# 1-Schematic_TW4_Main_board2.net
KiCad netlist of a schematic drawn in EasyEDA
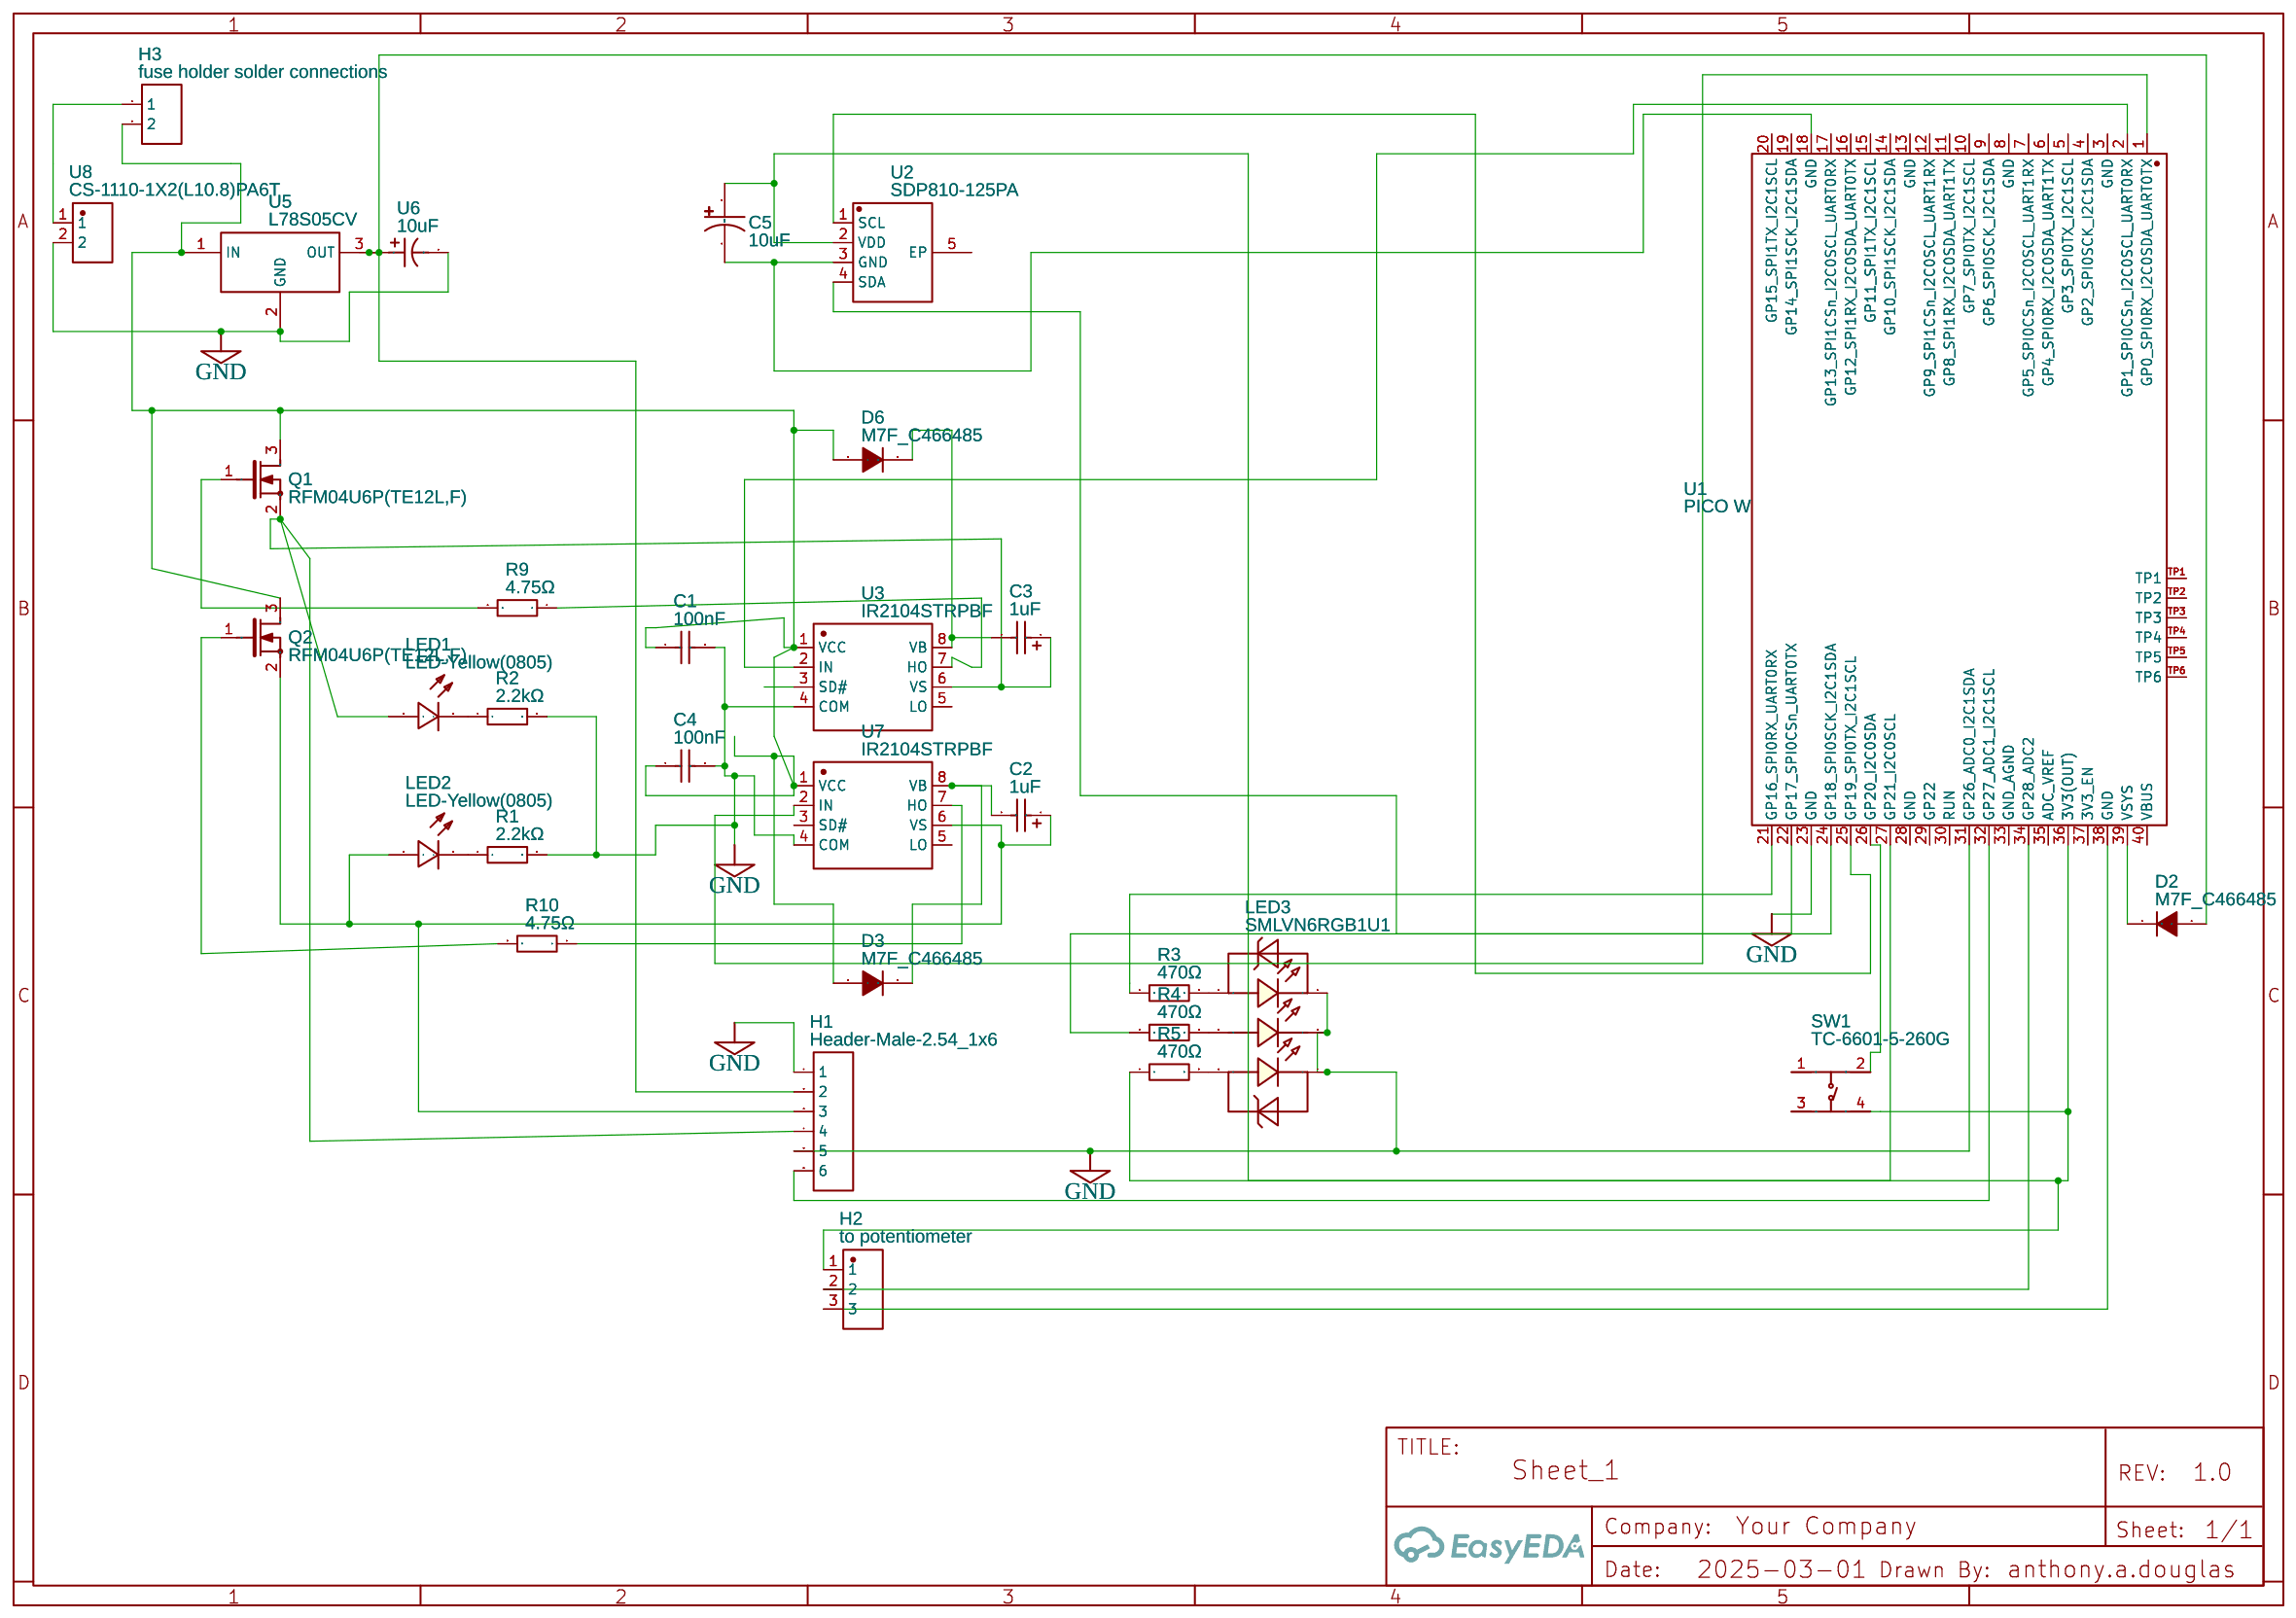
[diagram p0: schematic sheet]

(export (version "E")
  (design (tool "Eeschema 10.0.6"))
  (components
    (comp (ref "C1")
      (value "100nF")
      (fields (field (name "Manufacturer Part") "CGA3E2X7R1H104KT0Y0N") (field (name "Manufacturer") "TDK"))
      (libsource (lib "") (part "CGA3E2X7R1H104KT0Y0N"))
    )
    (comp (ref "C2")
      (value "1uF")
      (fields (field (name "Manufacturer Part") "TAJA105K035RNJ") (field (name "Manufacturer") "Kyocera AVX"))
      (libsource (lib "") (part "TAJA105K035RNJ"))
    )
    (comp (ref "C3")
      (value "1uF")
      (fields (field (name "Manufacturer Part") "TAJA105K035RNJ") (field (name "Manufacturer") "Kyocera AVX"))
      (libsource (lib "") (part "TAJA105K035RNJ"))
    )
    (comp (ref "C4")
      (value "100nF")
      (fields (field (name "Manufacturer Part") "CGA3E2X7R1H104KT0Y0N") (field (name "Manufacturer") "TDK"))
      (libsource (lib "") (part "CGA3E2X7R1H104KT0Y0N"))
    )
    (comp (ref "C5")
      (value "10uF")
      (fields (field (name "Manufacturer Part") "EEEFK1V100AR") (field (name "Manufacturer") "PANASONIC(松下)"))
      (libsource (lib "") (part "EEEFK1V100AR"))
    )
    (comp (ref "D2")
      (value "M7F_C466485")
      (fields (field (name "Manufacturer Part") "M7F") (field (name "Manufacturer") "High Diode(海德)"))
      (libsource (lib "") (part "M7F_C466485"))
    )
    (comp (ref "D3")
      (value "M7F_C466485")
      (fields (field (name "Manufacturer Part") "M7F") (field (name "Manufacturer") "High Diode(海德)"))
      (libsource (lib "") (part "M7F_C466485_1"))
    )
    (comp (ref "D6")
      (value "M7F_C466485")
      (fields (field (name "Manufacturer Part") "M7F") (field (name "Manufacturer") "High Diode(海德)"))
      (libsource (lib "") (part "M7F_C466485_1"))
    )
    (comp (ref "H1")
      (value "Header-Male-2.54_1x6")
      (fields (field (name "Manufacturer Part") "2.54-1x6P直针") (field (name "Manufacturer") "BOOMELE(博穆精密)"))
      (libsource (lib "") (part "Header-Male-2.54_1x6"))
    )
    (comp (ref "H2")
      (value "to potentiometer")
      (fields
        (field (name "Manufacturer Part") "HC-PM254-8.5H-1x3PW-02A")
        (field (name "Manufacturer") "HC(虹成电子)")
      )
      (libsource (lib "") (part "HC-PM254-8.5H-1X3PW"))
    )
    (comp (ref "H3") (value "fuse holder solder connections") (libsource (lib "") (part "HDR-F-2.54_1x2")))
    (comp (ref "LED1")
      (value "LED-Yellow(0805)")
      (fields
        (field (name "Manufacturer Part") "17-21SUYC/TR8")
        (field (name "Manufacturer") "Hubei KENTO Elec")
      )
      (libsource (lib "") (part "LED-Yellow(0805)"))
    )
    (comp (ref "LED2")
      (value "LED-Yellow(0805)")
      (fields
        (field (name "Manufacturer Part") "17-21SUYC/TR8")
        (field (name "Manufacturer") "Hubei KENTO Elec")
      )
      (libsource (lib "") (part "LED-Yellow(0805)"))
    )
    (comp (ref "LED3")
      (value "SMLVN6RGB1U1")
      (fields (field (name "Manufacturer") "ROHM(罗姆)"))
      (libsource (lib "") (part "SMLVN6RGB1U1"))
    )
    (comp (ref "Q1")
      (value "RFM04U6P(TE12L,F)")
      (fields (field (name "Manufacturer") "TOSHIBA(东芝)"))
      (libsource (lib "") (part "RFM04U6P(TE12L,F)"))
    )
    (comp (ref "Q2")
      (value "RFM04U6P(TE12L,F)")
      (fields (field (name "Manufacturer") "TOSHIBA(东芝)"))
      (libsource (lib "") (part "RFM04U6P(TE12L,F)"))
    )
    (comp (ref "R1")
      (value "2.2kΩ")
      (fields
        (field (name "Manufacturer Part") "0603WAF2201T5E")
        (field (name "Manufacturer") "UNI-ROYAL(厚声)")
      )
      (libsource (lib "") (part "0603WAF2201T5E"))
    )
    (comp (ref "R2")
      (value "2.2kΩ")
      (fields
        (field (name "Manufacturer Part") "0603WAF2201T5E")
        (field (name "Manufacturer") "UNI-ROYAL(厚声)")
      )
      (libsource (lib "") (part "0603WAF2201T5E"))
    )
    (comp (ref "R3")
      (value "470Ω")
      (fields
        (field (name "Manufacturer Part") "1206W4F4700T5E")
        (field (name "Manufacturer") "UNI-ROYAL(厚声)")
      )
      (libsource (lib "") (part "1206W4F4700T5E"))
    )
    (comp (ref "R4")
      (value "470Ω")
      (fields
        (field (name "Manufacturer Part") "1206W4F4700T5E")
        (field (name "Manufacturer") "UNI-ROYAL(厚声)")
      )
      (libsource (lib "") (part "1206W4F4700T5E"))
    )
    (comp (ref "R5")
      (value "470Ω")
      (fields
        (field (name "Manufacturer Part") "1206W4F4700T5E")
        (field (name "Manufacturer") "UNI-ROYAL(厚声)")
      )
      (libsource (lib "") (part "1206W4F4700T5E"))
    )
    (comp (ref "R9")
      (value "4.75Ω")
      (fields (field (name "Manufacturer Part") "RTT024R75FTH") (field (name "Manufacturer") "RALEC(旺诠)"))
      (libsource (lib "") (part "RTT024R75FTH"))
    )
    (comp (ref "R10")
      (value "4.75Ω")
      (fields (field (name "Manufacturer Part") "RTT024R75FTH") (field (name "Manufacturer") "RALEC(旺诠)"))
      (libsource (lib "") (part "RTT024R75FTH"))
    )
    (comp (ref "SW1")
      (value "TC-6601-5-260G")
      (fields (field (name "Manufacturer") "HCTL(华灿天禄)"))
      (libsource (lib "") (part "TC-6601-5-260G"))
    )
    (comp (ref "U1")
      (value "PICO W")
      (fields (field (name "Manufacturer") "Raspberry Pi(树莓派)"))
      (libsource (lib "") (part "PICO W"))
    )
    (comp (ref "U2")
      (value "SDP810-125PA")
      (fields
        (field (name "Manufacturer Part") "SDP810-125PA-D")
        (field (name "Manufacturer") "Sensirion(瑞士盛思锐)")
      )
      (libsource (lib "") (part "SDP810-125PA"))
    )
    (comp (ref "U3")
      (value "IR2104STRPBF")
      (fields (field (name "Manufacturer") "Infineon(英飞凌)"))
      (libsource (lib "") (part "IR2104STRPBF"))
    )
    (comp (ref "U5")
      (value "L78S05CV")
      (fields (field (name "Manufacturer") "ST(意法半导体)"))
      (libsource (lib "") (part "L78S05CV"))
    )
    (comp (ref "U6")
      (value "10uF")
      (fields (field (name "Manufacturer Part") "TMCP1A106MTRF") (field (name "Manufacturer") "VISHAY(威世)"))
      (libsource (lib "") (part "TMCP1A106MTRF"))
    )
    (comp (ref "U7")
      (value "IR2104STRPBF")
      (fields (field (name "Manufacturer") "Infineon(英飞凌)"))
      (libsource (lib "") (part "IR2104STRPBF"))
    )
    (comp (ref "U8")
      (value "CS-1110-1X2(L10.8)PA6T")
      (fields (field (name "Manufacturer") "CST(永丰盈)"))
      (libsource (lib "") (part "CS-1110-1X2(L10.8)PA6T"))
    )
  )
  (nets
    (net (code "1") (name "GND") (class "Default")
      (node (ref "C1") (pin "2") (pinfunction "2_2") (pintype "input"))
      (node (ref "C4") (pin "2") (pinfunction "2_2") (pintype "input"))
      (node (ref "H1") (pin "1") (pinfunction "1_1") (pintype "input"))
      (node (ref "H1") (pin "5") (pinfunction "5_5") (pintype "input"))
      (node (ref "LED3") (pin "4") (pinfunction "-_4") (pintype "unspecified"))
      (node (ref "LED3") (pin "5") (pinfunction "-_5") (pintype "unspecified"))
      (node (ref "LED3") (pin "6") (pinfunction "-_6") (pintype "unspecified"))
      (node (ref "R1") (pin "2") (pinfunction "2_2") (pintype "input"))
      (node (ref "R2") (pin "2") (pinfunction "2_2") (pintype "input"))
      (node (ref "U1") (pin "23") (pinfunction "GND_23") (pintype "unspecified"))
      (node (ref "U1") (pin "31") (pinfunction "GP26_ADC0_I2C1SDA_31") (pintype "unspecified"))
      (node (ref "U3") (pin "4") (pinfunction "COM_4") (pintype "unspecified"))
      (node (ref "U5") (pin "2") (pinfunction "GND_2") (pintype "passive"))
      (node (ref "U6") (pin "2") (pinfunction "2_2") (pintype "input"))
      (node (ref "U7") (pin "4") (pinfunction "COM_4") (pintype "unspecified"))
      (node (ref "U8") (pin "2") (pinfunction "2_2") (pintype "unspecified"))
    )
    (net (code "2") (name "Net-(D2-A)") (class "Default")
      (node (ref "D2") (pin "2") (pinfunction "A_2") (pintype "unspecified"))
      (node (ref "H1") (pin "2") (pinfunction "2_2") (pintype "input"))
      (node (ref "U5") (pin "3") (pinfunction "OUT_3") (pintype "passive"))
      (node (ref "U6") (pin "1") (pinfunction "1_1") (pintype "input"))
    )
    (net (code "3") (name "Net-(D2-C)") (class "Default")
      (node (ref "D2") (pin "1") (pinfunction "C_1") (pintype "unspecified"))
      (node (ref "U1") (pin "39") (pinfunction "VSYS_39") (pintype "unspecified"))
    )
    (net (code "4") (name "Net-(D3-A)") (class "Default")
      (node (ref "C1") (pin "1") (pinfunction "1_1") (pintype "input"))
      (node (ref "C4") (pin "1") (pinfunction "1_1") (pintype "input"))
      (node (ref "D3") (pin "2") (pinfunction "A_2") (pintype "unspecified"))
      (node (ref "D6") (pin "2") (pinfunction "A_2") (pintype "unspecified"))
      (node (ref "H3") (pin "2") (pinfunction "2_2") (pintype "input"))
      (node (ref "Q1") (pin "3") (pinfunction "D_3") (pintype "unspecified"))
      (node (ref "Q2") (pin "3") (pinfunction "D_3") (pintype "unspecified"))
      (node (ref "U3") (pin "1") (pinfunction "VCC_1") (pintype "unspecified"))
      (node (ref "U5") (pin "1") (pinfunction "IN_1") (pintype "passive"))
      (node (ref "U7") (pin "1") (pinfunction "VCC_1") (pintype "unspecified"))
    )
    (net (code "5") (name "Net-(D3-C)") (class "Default")
      (node (ref "C2") (pin "2") (pinfunction "2_2") (pintype "input"))
      (node (ref "D3") (pin "1") (pinfunction "C_1") (pintype "unspecified"))
      (node (ref "U7") (pin "8") (pinfunction "VB_8") (pintype "unspecified"))
    )
    (net (code "6") (name "Net-(D6-C)") (class "Default")
      (node (ref "C3") (pin "2") (pinfunction "2_2") (pintype "input"))
      (node (ref "D6") (pin "1") (pinfunction "C_1") (pintype "unspecified"))
      (node (ref "U3") (pin "8") (pinfunction "VB_8") (pintype "unspecified"))
    )
    (net (code "7") (name "Net-(H2-Pad3)") (class "Default")
      (node (ref "H2") (pin "3") (pinfunction "3_3") (pintype "unspecified"))
      (node (ref "U1") (pin "38") (pinfunction "GND_38") (pintype "unspecified"))
    )
    (net (code "8") (name "Net-(H3-Pad1)") (class "Default")
      (node (ref "H3") (pin "1") (pinfunction "1_1") (pintype "input"))
      (node (ref "U8") (pin "1") (pinfunction "1_1") (pintype "unspecified"))
    )
    (net (code "9") (name "Net-(LED1-+)") (class "Default")
      (node (ref "C3") (pin "1") (pinfunction "1_1") (pintype "input"))
      (node (ref "H1") (pin "4") (pinfunction "4_4") (pintype "input"))
      (node (ref "LED1") (pin "1") (pinfunction "+_1") (pintype "unspecified"))
      (node (ref "Q1") (pin "2") (pinfunction "S_2") (pintype "unspecified"))
      (node (ref "U3") (pin "6") (pinfunction "VS_6") (pintype "unspecified"))
    )
    (net (code "10") (name "Net-(LED1--)") (class "Default")
      (node (ref "LED1") (pin "2") (pinfunction "-_2") (pintype "unspecified"))
      (node (ref "R2") (pin "1") (pinfunction "1_1") (pintype "input"))
    )
    (net (code "11") (name "Net-(LED2-+)") (class "Default")
      (node (ref "C2") (pin "1") (pinfunction "1_1") (pintype "input"))
      (node (ref "H1") (pin "3") (pinfunction "3_3") (pintype "input"))
      (node (ref "LED2") (pin "1") (pinfunction "+_1") (pintype "unspecified"))
      (node (ref "Q2") (pin "2") (pinfunction "S_2") (pintype "unspecified"))
      (node (ref "U7") (pin "6") (pinfunction "VS_6") (pintype "unspecified"))
    )
    (net (code "12") (name "Net-(LED2--)") (class "Default")
      (node (ref "LED2") (pin "2") (pinfunction "-_2") (pintype "unspecified"))
      (node (ref "R1") (pin "1") (pinfunction "1_1") (pintype "input"))
    )
    (net (code "13") (name "Net-(LED3-+-Pad1)") (class "Default")
      (node (ref "LED3") (pin "1") (pinfunction "+_1") (pintype "unspecified"))
      (node (ref "R3") (pin "2") (pinfunction "2_2") (pintype "input"))
    )
    (net (code "14") (name "Net-(LED3-+-Pad2)") (class "Default")
      (node (ref "LED3") (pin "2") (pinfunction "+_2") (pintype "unspecified"))
      (node (ref "R4") (pin "2") (pinfunction "2_2") (pintype "input"))
    )
    (net (code "15") (name "Net-(LED3-+-Pad3)") (class "Default")
      (node (ref "LED3") (pin "3") (pinfunction "+_3") (pintype "unspecified"))
      (node (ref "R5") (pin "2") (pinfunction "2_2") (pintype "input"))
    )
    (net (code "16") (name "Net-(Q1-G)") (class "Default")
      (node (ref "Q1") (pin "1") (pinfunction "G_1") (pintype "unspecified"))
      (node (ref "R9") (pin "2") (pinfunction "2_2") (pintype "unspecified"))
    )
    (net (code "17") (name "Net-(Q2-G)") (class "Default")
      (node (ref "Q2") (pin "1") (pinfunction "G_1") (pintype "unspecified"))
      (node (ref "R10") (pin "2") (pinfunction "2_2") (pintype "unspecified"))
    )
    (net (code "18") (name "Net-(U1-3V3(OUT))") (class "Default")
      (node (ref "C5") (pin "1") (pinfunction "1_1") (pintype "unspecified"))
      (node (ref "H2") (pin "1") (pinfunction "1_1") (pintype "unspecified"))
      (node (ref "SW1") (pin "4") (pinfunction "4_4") (pintype "unspecified"))
      (node (ref "U1") (pin "36") (pinfunction "3V3(OUT)_36") (pintype "unspecified"))
      (node (ref "U2") (pin "2") (pinfunction "VDD_2") (pintype "unspecified"))
    )
    (net (code "19") (name "Net-(U1-GP0_SPI0RX_I2C0SDA_UART0TX)") (class "Default")
      (node (ref "U1") (pin "1") (pinfunction "GP0_SPI0RX_I2C0SDA_UART0TX_1") (pintype "unspecified"))
      (node (ref "U7") (pin "2") (pinfunction "IN_2") (pintype "unspecified"))
    )
    (net (code "20") (name "Net-(U1-GP1_SPI0CSn_I2C0SCL_UART0RX)") (class "Default")
      (node (ref "U1") (pin "2") (pinfunction "GP1_SPI0CSn_I2C0SCL_UART0RX_2") (pintype "unspecified"))
      (node (ref "U3") (pin "2") (pinfunction "IN_2") (pintype "unspecified"))
    )
    (net (code "21") (name "Net-(U1-GP16_SPI0RX_UART0RX)") (class "Default")
      (node (ref "R3") (pin "1") (pinfunction "1_1") (pintype "input"))
      (node (ref "U1") (pin "21") (pinfunction "GP16_SPI0RX_UART0RX_21") (pintype "unspecified"))
    )
    (net (code "22") (name "Net-(U1-GP17_SPI0CSn_UART0TX)") (class "Default")
      (node (ref "R4") (pin "1") (pinfunction "1_1") (pintype "input"))
      (node (ref "U1") (pin "22") (pinfunction "GP17_SPI0CSn_UART0TX_22") (pintype "unspecified"))
    )
    (net (code "23") (name "Net-(U1-GP18_SPI0SCK_I2C1SDA)") (class "Default")
      (node (ref "U1") (pin "24") (pinfunction "GP18_SPI0SCK_I2C1SDA_24") (pintype "unspecified"))
      (node (ref "U2") (pin "4") (pinfunction "SDA_4") (pintype "unspecified"))
    )
    (net (code "24") (name "Net-(U1-GP19_SPI0TX_I2C1SCL)") (class "Default")
      (node (ref "U1") (pin "25") (pinfunction "GP19_SPI0TX_I2C1SCL_25") (pintype "unspecified"))
      (node (ref "U2") (pin "1") (pinfunction "SCL_1") (pintype "unspecified"))
    )
    (net (code "25") (name "Net-(U1-GP20_I2C0SDA)") (class "Default")
      (node (ref "SW1") (pin "2") (pinfunction "2_2") (pintype "unspecified"))
      (node (ref "U1") (pin "26") (pinfunction "GP20_I2C0SDA_26") (pintype "unspecified"))
    )
    (net (code "26") (name "Net-(U1-GP21_I2C0SCL)") (class "Default")
      (node (ref "R5") (pin "1") (pinfunction "1_1") (pintype "input"))
      (node (ref "U1") (pin "27") (pinfunction "GP21_I2C0SCL_27") (pintype "unspecified"))
    )
    (net (code "27") (name "Net-(U1-GP27_ADC1_I2C1SCL)") (class "Default")
      (node (ref "H1") (pin "6") (pinfunction "6_6") (pintype "input"))
      (node (ref "U1") (pin "32") (pinfunction "GP27_ADC1_I2C1SCL_32") (pintype "unspecified"))
    )
    (net (code "28") (name "Net-(U1-GP28_ADC2)") (class "Default")
      (node (ref "H2") (pin "2") (pinfunction "2_2") (pintype "unspecified"))
      (node (ref "U1") (pin "34") (pinfunction "GP28_ADC2_34") (pintype "unspecified"))
    )
    (net (code "29") (name "Net-(U2-GND)") (class "Default")
      (node (ref "C5") (pin "2") (pinfunction "2_2") (pintype "unspecified"))
      (node (ref "U1") (pin "18") (pinfunction "GND_18") (pintype "unspecified"))
      (node (ref "U2") (pin "3") (pinfunction "GND_3") (pintype "unspecified"))
    )
    (net (code "30") (name "Net-(U3-HO)") (class "Default")
      (node (ref "R9") (pin "1") (pinfunction "1_1") (pintype "unspecified"))
      (node (ref "U3") (pin "7") (pinfunction "HO_7") (pintype "unspecified"))
    )
    (net (code "31") (name "Net-(U7-HO)") (class "Default")
      (node (ref "R10") (pin "1") (pinfunction "1_1") (pintype "unspecified"))
      (node (ref "U7") (pin "7") (pinfunction "HO_7") (pintype "unspecified"))
    )
    (net (code "32") (name "unconnected-(SW1-Pad1)") (class "Default")
      (node (ref "SW1") (pin "1") (pinfunction "1_1") (pintype "unspecified"))
    )
    (net (code "33") (name "unconnected-(SW1-Pad3)") (class "Default")
      (node (ref "SW1") (pin "3") (pinfunction "3_3") (pintype "unspecified"))
    )
    (net (code "34") (name "unconnected-(U1-3V3_EN-Pad37)") (class "Default")
      (node (ref "U1") (pin "37") (pinfunction "3V3_EN_37") (pintype "unspecified"))
    )
    (net (code "35") (name "unconnected-(U1-ADC_VREF-Pad35)") (class "Default")
      (node (ref "U1") (pin "35") (pinfunction "ADC_VREF_35") (pintype "unspecified"))
    )
    (net (code "36") (name "unconnected-(U1-GND-Pad3)") (class "Default")
      (node (ref "U1") (pin "3") (pinfunction "GND_3") (pintype "unspecified"))
    )
    (net (code "37") (name "unconnected-(U1-GND-Pad8)") (class "Default")
      (node (ref "U1") (pin "8") (pinfunction "GND_8") (pintype "unspecified"))
    )
    (net (code "38") (name "unconnected-(U1-GND-Pad13)") (class "Default")
      (node (ref "U1") (pin "13") (pinfunction "GND_13") (pintype "unspecified"))
    )
    (net (code "39") (name "unconnected-(U1-GND-Pad28)") (class "Default")
      (node (ref "U1") (pin "28") (pinfunction "GND_28") (pintype "unspecified"))
    )
    (net (code "40") (name "unconnected-(U1-GND_AGND-Pad33)") (class "Default")
      (node (ref "U1") (pin "33") (pinfunction "GND_AGND_33") (pintype "unspecified"))
    )
    (net (code "41") (name "unconnected-(U1-GP2_SPI0SCK_I2C1SDA-Pad4)") (class "Default")
      (node (ref "U1") (pin "4") (pinfunction "GP2_SPI0SCK_I2C1SDA_4") (pintype "unspecified"))
    )
    (net (code "42") (name "unconnected-(U1-GP3_SPI0TX_I2C1SCL-Pad5)") (class "Default")
      (node (ref "U1") (pin "5") (pinfunction "GP3_SPI0TX_I2C1SCL_5") (pintype "unspecified"))
    )
    (net (code "43") (name "unconnected-(U1-GP4_SPI0RX_I2C0SDA_UART1TX-Pad6)") (class "Default")
      (node (ref "U1") (pin "6") (pinfunction "GP4_SPI0RX_I2C0SDA_UART1TX_6") (pintype "unspecified"))
    )
    (net (code "44") (name "unconnected-(U1-GP5_SPI0CSn_I2C0SCL_UART1RX-Pad7)") (class "Default")
      (node (ref "U1") (pin "7") (pinfunction "GP5_SPI0CSn_I2C0SCL_UART1RX_7") (pintype "unspecified"))
    )
    (net (code "45") (name "unconnected-(U1-GP6_SPI0SCK_I2C1SDA-Pad9)") (class "Default")
      (node (ref "U1") (pin "9") (pinfunction "GP6_SPI0SCK_I2C1SDA_9") (pintype "unspecified"))
    )
    (net (code "46") (name "unconnected-(U1-GP7_SPI0TX_I2C1SCL-Pad10)") (class "Default")
      (node (ref "U1") (pin "10") (pinfunction "GP7_SPI0TX_I2C1SCL_10") (pintype "unspecified"))
    )
    (net (code "47") (name "unconnected-(U1-GP8_SPI1RX_I2C0SDA_UART1TX-Pad11)") (class "Default")
      (node (ref "U1") (pin "11") (pinfunction "GP8_SPI1RX_I2C0SDA_UART1TX_11") (pintype "unspecified"))
    )
    (net (code "48") (name "unconnected-(U1-GP9_SPI1CSn_I2C0SCL_UART1RX-Pad12)") (class "Default")
      (node (ref "U1") (pin "12") (pinfunction "GP9_SPI1CSn_I2C0SCL_UART1RX_12") (pintype "unspecified"))
    )
    (net (code "49") (name "unconnected-(U1-GP10_SPI1SCK_I2C1SDA-Pad14)") (class "Default")
      (node (ref "U1") (pin "14") (pinfunction "GP10_SPI1SCK_I2C1SDA_14") (pintype "unspecified"))
    )
    (net (code "50") (name "unconnected-(U1-GP11_SPI1TX_I2C1SCL-Pad15)") (class "Default")
      (node (ref "U1") (pin "15") (pinfunction "GP11_SPI1TX_I2C1SCL_15") (pintype "unspecified"))
    )
    (net (code "51") (name "unconnected-(U1-GP12_SPI1RX_I2C0SDA_UART0TX-Pad16)") (class "Default")
      (node (ref "U1") (pin "16") (pinfunction "GP12_SPI1RX_I2C0SDA_UART0TX_16") (pintype "unspecified"))
    )
    (net (code "52") (name "unconnected-(U1-GP13_SPI1CSn_I2C0SCL_UART0RX-Pad17)") (class "Default")
      (node (ref "U1") (pin "17") (pinfunction "GP13_SPI1CSn_I2C0SCL_UART0RX_17") (pintype "unspecified"))
    )
    (net (code "53") (name "unconnected-(U1-GP14_SPI1SCK_I2C1SDA-Pad19)") (class "Default")
      (node (ref "U1") (pin "19") (pinfunction "GP14_SPI1SCK_I2C1SDA_19") (pintype "unspecified"))
    )
    (net (code "54") (name "unconnected-(U1-GP15_SPI1TX_I2C1SCL-Pad20)") (class "Default")
      (node (ref "U1") (pin "20") (pinfunction "GP15_SPI1TX_I2C1SCL_20") (pintype "unspecified"))
    )
    (net (code "55") (name "unconnected-(U1-GP22-Pad29)") (class "Default")
      (node (ref "U1") (pin "29") (pinfunction "GP22_29") (pintype "unspecified"))
    )
    (net (code "56") (name "unconnected-(U1-PadTP1)") (class "Default")
      (node (ref "U1") (pin "TP1") (pinfunction "TP1_TP1") (pintype "unspecified"))
    )
    (net (code "57") (name "unconnected-(U1-PadTP2)") (class "Default")
      (node (ref "U1") (pin "TP2") (pinfunction "TP2_TP2") (pintype "unspecified"))
    )
    (net (code "58") (name "unconnected-(U1-PadTP3)") (class "Default")
      (node (ref "U1") (pin "TP3") (pinfunction "TP3_TP3") (pintype "unspecified"))
    )
    (net (code "59") (name "unconnected-(U1-PadTP4)") (class "Default")
      (node (ref "U1") (pin "TP4") (pinfunction "TP4_TP4") (pintype "unspecified"))
    )
    (net (code "60") (name "unconnected-(U1-PadTP5)") (class "Default")
      (node (ref "U1") (pin "TP5") (pinfunction "TP5_TP5") (pintype "unspecified"))
    )
    (net (code "61") (name "unconnected-(U1-PadTP6)") (class "Default")
      (node (ref "U1") (pin "TP6") (pinfunction "TP6_TP6") (pintype "unspecified"))
    )
    (net (code "62") (name "unconnected-(U1-RUN-Pad30)") (class "Default")
      (node (ref "U1") (pin "30") (pinfunction "RUN_30") (pintype "unspecified"))
    )
    (net (code "63") (name "unconnected-(U1-VBUS-Pad40)") (class "Default")
      (node (ref "U1") (pin "40") (pinfunction "VBUS_40") (pintype "unspecified"))
    )
    (net (code "64") (name "unconnected-(U2-EP-Pad5)") (class "Default")
      (node (ref "U2") (pin "5") (pinfunction "EP_5") (pintype "unspecified"))
    )
    (net (code "65") (name "unconnected-(U3-LO-Pad5)") (class "Default")
      (node (ref "U3") (pin "5") (pinfunction "LO_5") (pintype "unspecified"))
    )
    (net (code "66") (name "unconnected-(U3-SD#-Pad3)") (class "Default")
      (node (ref "U3") (pin "3") (pinfunction "SD#_3") (pintype "unspecified"))
    )
    (net (code "67") (name "unconnected-(U7-LO-Pad5)") (class "Default")
      (node (ref "U7") (pin "5") (pinfunction "LO_5") (pintype "unspecified"))
    )
    (net (code "68") (name "unconnected-(U7-SD#-Pad3)") (class "Default")
      (node (ref "U7") (pin "3") (pinfunction "SD#_3") (pintype "unspecified"))
    )
  )
)
